# Gateway.net
KiCad netlist of a schematic drawn in Altium Designer
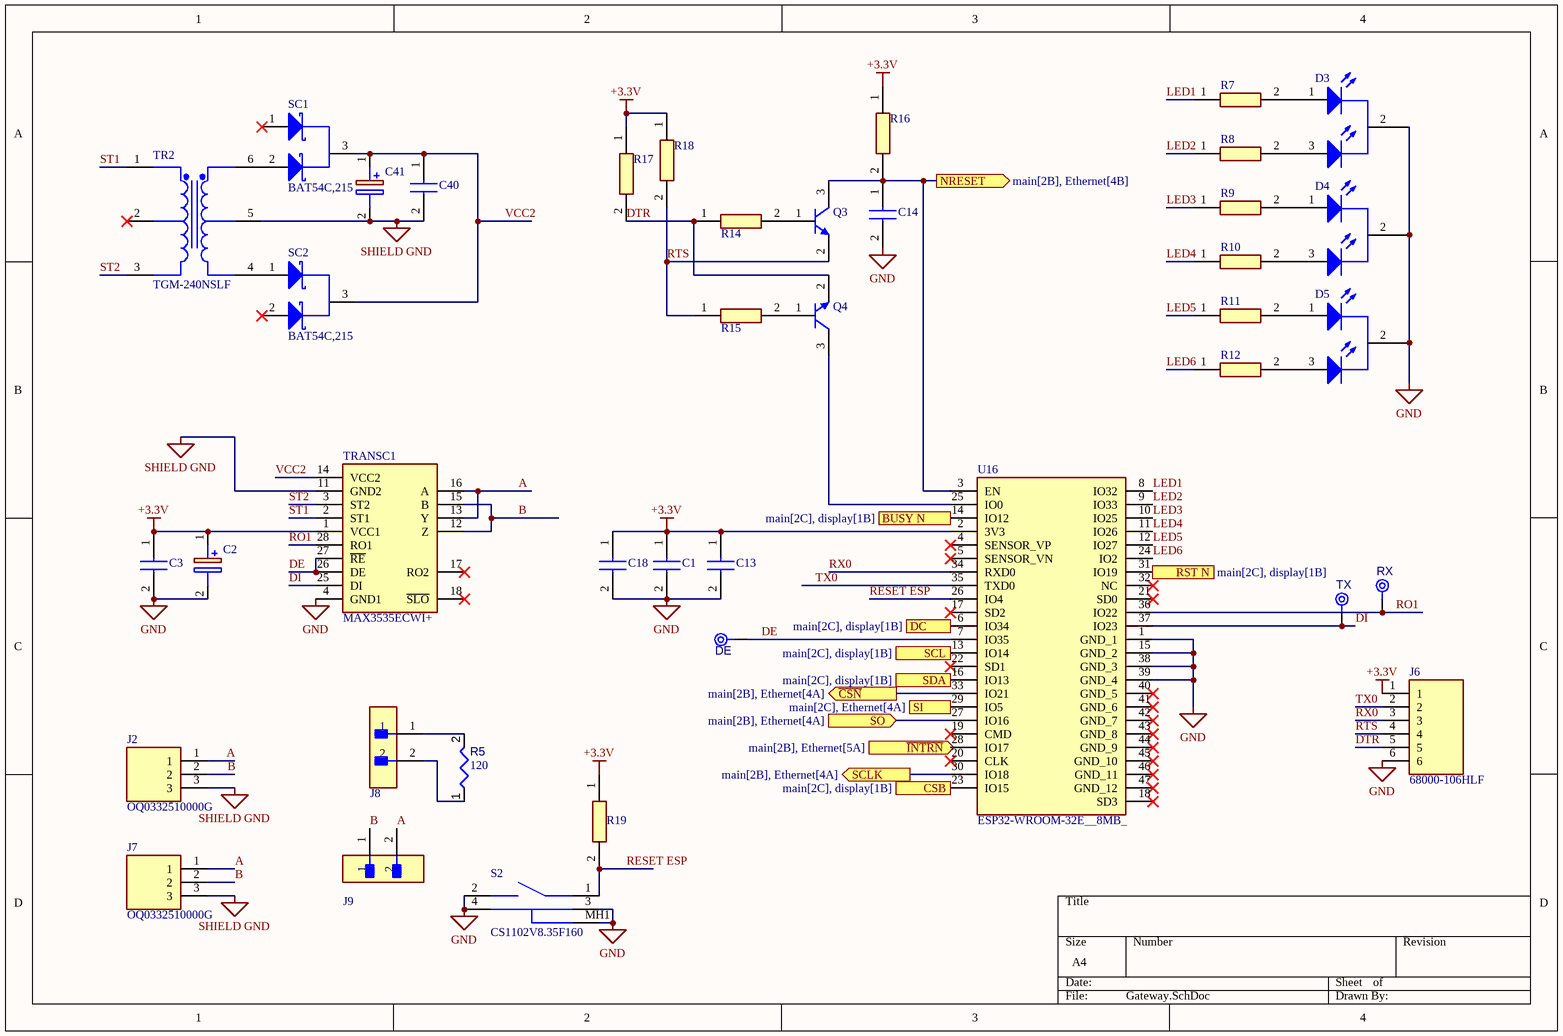
[diagram p0: Gateway.SchDoc]

(export (version "E")
  (design (tool "Eeschema 10.0.6"))
  (components
    (comp (ref "C1")
      (value "C1005X7R1C104KT")
      (footprint "SamacSys:CAPC1005X55N")
      (description "Capacitor 100n")
      (libsource (lib "*") (part "C1005X7R1C104KT"))
    )
    (comp (ref "C2")
      (value "EDH106M016A9BAA")
      (footprint "SamacSys:CAPAE430X565N")
      (description "Capacitor Polarised 10u")
      (fields (field (name "MOUSER PART NUMBER") "80-EDH106M016A9BAA"))
      (libsource (lib "*") (part "EDH106M016A9BAA"))
    )
    (comp (ref "C3")
      (value "C1005X7R1C104KT")
      (footprint "SamacSys:CAPC1005X55N")
      (description "Capacitor 100n")
      (libsource (lib "*") (part "C1005X7R1C104KT"))
    )
    (comp (ref "C13")
      (value "CL05A106MP8NUB8")
      (footprint "SamacSys:CAPC1005X90N")
      (description "Capacitor 10u")
      (fields (field (name "MOUSER PART NUMBER") "187-CL05A106MP8NUB8"))
      (libsource (lib "*") (part "CL05A106MP8NUB8"))
    )
    (comp (ref "C14")
      (value "CL05A106MP8NUB8")
      (footprint "SamacSys:CAPC1005X90N")
      (description "Capacitor 10u")
      (fields (field (name "MOUSER PART NUMBER") "187-CL05A106MP8NUB8"))
      (libsource (lib "*") (part "CL05A106MP8NUB8"))
    )
    (comp (ref "C18")
      (value "CL05B103KO5NNNC")
      (footprint "SamacSys:CAPC1005X55N")
      (description "Capacitor 10n")
      (libsource (lib "*") (part "CL05B103KO5NNNC"))
    )
    (comp (ref "C40")
      (value "C1005X7R1C104KT")
      (footprint "SamacSys:CAPC1005X55N")
      (description "Capacitor 100n")
      (libsource (lib "*") (part "C1005X7R1C104KT"))
    )
    (comp (ref "C41")
      (value "EDH106M016A9BAA")
      (footprint "SamacSys:CAPAE430X565N")
      (description "Capacitor Polarised 10u")
      (fields (field (name "MOUSER PART NUMBER") "80-EDH106M016A9BAA"))
      (libsource (lib "*") (part "EDH106M016A9BAA"))
    )
    (comp (ref "D3")
      (value "LTL1BEKVJNN")
      (footprint "Lite-On_Inc._LTL1BEKVJNN_0")
      (description "No Description Available")
      (libsource (lib "LTL1BEKVJNN") (part "LTL1BEKVJNN"))
    )
    (comp (ref "D4")
      (value "LTL1BEKVJNN")
      (footprint "Lite-On_Inc._LTL1BEKVJNN_0")
      (description "No Description Available")
      (libsource (lib "LTL1BEKVJNN") (part "LTL1BEKVJNN"))
    )
    (comp (ref "D5")
      (value "LTL1BEKVJNN")
      (footprint "Lite-On_Inc._LTL1BEKVJNN_0")
      (description "No Description Available")
      (libsource (lib "LTL1BEKVJNN") (part "LTL1BEKVJNN"))
    )
    (comp (ref "DE")
      (value "TPAD6R")
      (footprint "TP06R")
      (description "0.6mm round")
      (libsource (lib "marina santos") (part "CMP-001-0001-4"))
    )
    (comp (ref "J2")
      (value "OQ0332510000G")
      (footprint "SamacSys:SHDRRA3W80P0X381_1X3_1262X920X720P")
      (description "Connector")
      (fields (field (name "MOUSER PART NUMBER") "649-220110-D031A01LF"))
      (libsource (lib "*") (part "OQ0332510000G"))
    )
    (comp (ref "J6")
      (value "68000-106HLF")
      (footprint "HDRV6W50P0X200_1X6_1200X200X530P")
      (description "Connector")
      (fields
        (field (name "MANUFACTURER_PART_NUMBER") "M22-2010605")
        (field (name "MOUSER PART NUMBER") "855-M22-2010605")
      )
      (libsource (lib "*") (part "M22-2010605"))
    )
    (comp (ref "J7")
      (value "OQ0332510000G")
      (footprint "SamacSys:SHDRRA3W80P0X381_1X3_1262X920X720P")
      (description "Connector")
      (fields (field (name "MOUSER PART NUMBER") "649-220110-D031A01LF"))
      (libsource (lib "*") (part "OQ0332510000G"))
    )
    (comp (ref "J8")
      (value "68000-102HLF")
      (footprint "Amphenol_ICC_-_FCI_0_MFG")
      (libsource (lib "") (part "68000-102HLF_1"))
    )
    (comp (ref "J9")
      (value "68000-102HLF")
      (footprint "Amphenol_ICC_-_FCI_0_MFG")
      (libsource (lib "Conn_Amphenol_ICC_-_FCI_68000-102HLF_eec") (part "68000-102HLF"))
    )
    (comp (ref "Q3")
      (value "MMBT2222ALT1G")
      (footprint "SamacSys:SOT96P237X111-3N")
      (description "Integrated Circuit")
      (fields (field (name "MOUSER PART NUMBER") "863-MMBT2222ALT1G"))
      (libsource (lib "SamacSys") (part "MMBT2222ALT1G"))
    )
    (comp (ref "Q4")
      (value "MMBT2222ALT1G")
      (footprint "SamacSys:SOT96P237X111-3N")
      (description "Integrated Circuit")
      (fields (field (name "MOUSER PART NUMBER") "863-MMBT2222ALT1G"))
      (libsource (lib "SamacSys") (part "MMBT2222ALT1G"))
    )
    (comp (ref "R5")
      (value "120")
      (footprint "RESC0805(2012)_L")
      (description "Chip Resistor 120 ohms +1%")
      (fields (field (name "TOLERANCE") "5%") (field (name "POWER") "125mW"))
      (libsource (lib "marina santos") (part "RES-2"))
    )
    (comp (ref "R7")
      (value "RC0402FR-071KL")
      (footprint "SamacSys:RESC1005X40N")
      (description "Resistor")
      (fields (field (name "MOUSER PART NUMBER") "603-RC0402FR-071KL"))
      (libsource (lib "*") (part "RC0402FR-071KL"))
    )
    (comp (ref "R8")
      (value "RC0402FR-071KL")
      (footprint "SamacSys:RESC1005X40N")
      (description "Resistor")
      (fields (field (name "MOUSER PART NUMBER") "603-RC0402FR-071KL"))
      (libsource (lib "*") (part "RC0402FR-071KL"))
    )
    (comp (ref "R9")
      (value "RC0402FR-071KL")
      (footprint "SamacSys:RESC1005X40N")
      (description "Resistor")
      (fields (field (name "MOUSER PART NUMBER") "603-RC0402FR-071KL"))
      (libsource (lib "*") (part "RC0402FR-071KL"))
    )
    (comp (ref "R10")
      (value "RC0402FR-071KL")
      (footprint "SamacSys:RESC1005X40N")
      (description "Resistor")
      (fields (field (name "MOUSER PART NUMBER") "603-RC0402FR-071KL"))
      (libsource (lib "*") (part "RC0402FR-071KL"))
    )
    (comp (ref "R11")
      (value "RC0402FR-071KL")
      (footprint "SamacSys:RESC1005X40N")
      (description "Resistor")
      (fields (field (name "MOUSER PART NUMBER") "603-RC0402FR-071KL"))
      (libsource (lib "*") (part "RC0402FR-071KL"))
    )
    (comp (ref "R12")
      (value "RC0402FR-071KL")
      (footprint "SamacSys:RESC1005X40N")
      (description "Resistor")
      (fields (field (name "MOUSER PART NUMBER") "603-RC0402FR-071KL"))
      (libsource (lib "*") (part "RC0402FR-071KL"))
    )
    (comp (ref "R14")
      (value "RC0402FR-0710KL")
      (footprint "SamacSys:RESC1005X40N")
      (description "Resistor 10K")
      (fields (field (name "MOUSER PART NUMBER") "603-RC0402FR-0710KL"))
      (libsource (lib "") (part "RC0402FR-0710KL_1"))
    )
    (comp (ref "R15")
      (value "RC0402FR-0710KL")
      (footprint "SamacSys:RESC1005X40N")
      (description "Resistor 10K")
      (fields (field (name "MOUSER PART NUMBER") "603-RC0402FR-0710KL"))
      (libsource (lib "") (part "RC0402FR-0710KL_1"))
    )
    (comp (ref "R16")
      (value "RC0402FR-0710KL")
      (footprint "SamacSys:RESC1005X40N")
      (description "Resistor 10K")
      (fields (field (name "MOUSER PART NUMBER") "603-RC0402FR-0710KL"))
      (libsource (lib "*") (part "RC0402FR-0710KL"))
    )
    (comp (ref "R17")
      (value "RC0402FR-0710KL")
      (footprint "SamacSys:RESC1005X40N")
      (description "Resistor 10K")
      (fields (field (name "MOUSER PART NUMBER") "603-RC0402FR-0710KL"))
      (libsource (lib "*") (part "RC0402FR-0710KL"))
    )
    (comp (ref "R18")
      (value "RC0402FR-0710KL")
      (footprint "SamacSys:RESC1005X40N")
      (description "Resistor 10K")
      (fields (field (name "MOUSER PART NUMBER") "603-RC0402FR-0710KL"))
      (libsource (lib "*") (part "RC0402FR-0710KL"))
    )
    (comp (ref "R19")
      (value "RC0402FR-0710KL")
      (footprint "SamacSys:RESC1005X40N")
      (description "Resistor 10K")
      (fields (field (name "MOUSER PART NUMBER") "603-RC0402FR-0710KL"))
      (libsource (lib "*") (part "RC0402FR-0710KL"))
    )
    (comp (ref "RX")
      (value "TPAD6R")
      (footprint "TP06R")
      (description "0.6mm round")
      (libsource (lib "marina santos") (part "CMP-001-0001-4"))
    )
    (comp (ref "S2")
      (value "CS1102V8.35F160")
      (footprint "SamacSys:CS1102V385F260")
      (description "Switch")
      (fields (field (name "MANUFACTURER_PART_NUMBER") "CS1102V3.85F260"))
      (libsource (lib "SamacSys") (part "CS1102V3.85F260"))
    )
    (comp (ref "SC1")
      (value "BAT54C,215")
      (footprint "SamacSys:BAT54C215")
      (description "Schottky Diode")
      (fields (field (name "MOUSER PART NUMBER") "771-BAT54C-T/R"))
      (libsource (lib "SamacSys") (part "BAT54C,215"))
    )
    (comp (ref "SC2")
      (value "BAT54C,215")
      (footprint "SamacSys:BAT54C215")
      (description "Schottky Diode")
      (fields (field (name "MOUSER PART NUMBER") "771-BAT54C-T/R"))
      (libsource (lib "SamacSys") (part "BAT54C,215"))
    )
    (comp (ref "TR2")
      (value "TGM-240NSLF")
      (footprint "SamacSys:TGM240NSLF")
      (description "Connector")
      (fields (field (name "MOUSER PART NUMBER") "493-TGM-240NSLF"))
      (libsource (lib "SamacSys") (part "TGM-240NSLF"))
    )
    (comp (ref "TRANSC1")
      (value "MAX3535ECWI+")
      (footprint "SamacSys:MAX3535ECWI")
      (description "Integrated Circuit")
      (fields (field (name "MOUSER PART NUMBER") "700-MAX3535ECWI"))
      (libsource (lib "SamacSys") (part "MAX3535ECWI+"))
    )
    (comp (ref "TX")
      (value "TPAD6R")
      (footprint "TP06R")
      (description "0.6mm round")
      (libsource (lib "marina santos") (part "CMP-001-0001-4"))
    )
    (comp (ref "U16")
      (value "ESP32-WROOM-32E__8MB_")
      (footprint "SamacSys:ESP32WROOM32E8MB")
      (description "Integrated Circuit")
      (fields
        (field (name "MANUFACTURER_PART_NUMBER") "ESP32-WROOM-32E (8MB)")
        (field (name "MOUSER PART NUMBER") "356-ESP32WRM32E164PH")
      )
      (libsource (lib "SamacSys") (part "ESP32-WROOM-32E__8MB_"))
    )
  )
  (nets
    (net (code "1") (name "+3.3V") (class "Default")
      (node (ref "C1") (pin "1") (pinfunction "1_1") (pintype "passive"))
      (node (ref "C13") (pin "1") (pinfunction "1_1") (pintype "passive"))
      (node (ref "C18") (pin "1") (pinfunction "1_1") (pintype "passive"))
      (node (ref "C2") (pin "1") (pinfunction "+_1") (pintype "passive"))
      (node (ref "C3") (pin "1") (pinfunction "1_1") (pintype "passive"))
      (node (ref "J6") (pin "1") (pinfunction "1_1") (pintype "passive"))
      (node (ref "R16") (pin "1") (pinfunction "1_1") (pintype "passive"))
      (node (ref "R17") (pin "1") (pinfunction "1_1") (pintype "passive"))
      (node (ref "R18") (pin "1") (pinfunction "1_1") (pintype "passive"))
      (node (ref "R19") (pin "1") (pinfunction "1_1") (pintype "passive"))
      (node (ref "TRANSC1") (pin "1") (pinfunction "VCC1_1") (pintype "passive"))
      (node (ref "U16") (pin "2") (pinfunction "3V3_2") (pintype "passive"))
    )
    (net (code "2") (name "/A") (class "Default")
      (node (ref "J2") (pin "1") (pinfunction "1_1") (pintype "passive"))
      (node (ref "J7") (pin "1") (pinfunction "1_1") (pintype "passive"))
      (node (ref "J9") (pin "2") (pinfunction "2_2") (pintype "passive"))
      (node (ref "TRANSC1") (pin "13") (pinfunction "Y_13") (pintype "passive"))
      (node (ref "TRANSC1") (pin "16") (pinfunction "A_16") (pintype "passive"))
    )
    (net (code "3") (name "/B") (class "Default")
      (node (ref "J2") (pin "2") (pinfunction "2_2") (pintype "passive"))
      (node (ref "J7") (pin "2") (pinfunction "2_2") (pintype "passive"))
      (node (ref "J9") (pin "1") (pinfunction "1_1") (pintype "passive"))
      (node (ref "TRANSC1") (pin "12") (pinfunction "Z_12") (pintype "passive"))
      (node (ref "TRANSC1") (pin "15") (pinfunction "B_15") (pintype "passive"))
    )
    (net (code "4") (name "/BUSY N") (class "Default")
      (node (ref "U16") (pin "14") (pinfunction "IO12_14") (pintype "passive"))
    )
    (net (code "5") (name "/CSB") (class "Default")
      (node (ref "U16") (pin "23") (pinfunction "IO15_23") (pintype "passive"))
    )
    (net (code "6") (name "/DC") (class "Default")
      (node (ref "U16") (pin "6") (pinfunction "IO34_6") (pintype "passive"))
    )
    (net (code "7") (name "/DE") (class "Default")
      (node (ref "DE") (pin "1") (pinfunction "TP_1") (pintype "passive"))
      (node (ref "TRANSC1") (pin "26") (pinfunction "DE_26") (pintype "passive"))
      (node (ref "TRANSC1") (pin "27") (pinfunction "~{RE}_27") (pintype "passive"))
      (node (ref "U16") (pin "7") (pinfunction "IO35_7") (pintype "passive"))
    )
    (net (code "8") (name "/DI") (class "Default")
      (node (ref "TRANSC1") (pin "25") (pinfunction "DI_25") (pintype "passive"))
      (node (ref "TX") (pin "1") (pinfunction "TP_1") (pintype "passive"))
      (node (ref "U16") (pin "37") (pinfunction "IO23_37") (pintype "passive"))
    )
    (net (code "9") (name "/DTR") (class "Default")
      (node (ref "J6") (pin "5") (pinfunction "5_5") (pintype "passive"))
      (node (ref "Q4") (pin "2") (pinfunction "E_2") (pintype "passive"))
      (node (ref "R14") (pin "1") (pinfunction "1_1") (pintype "passive"))
      (node (ref "R17") (pin "2") (pinfunction "2_2") (pintype "passive"))
    )
    (net (code "10") (name "/LED1") (class "Default")
      (node (ref "R7") (pin "1") (pinfunction "1_1") (pintype "passive"))
      (node (ref "U16") (pin "8") (pinfunction "IO32_8") (pintype "passive"))
    )
    (net (code "11") (name "/LED2") (class "Default")
      (node (ref "R8") (pin "1") (pinfunction "1_1") (pintype "passive"))
      (node (ref "U16") (pin "9") (pinfunction "IO33_9") (pintype "passive"))
    )
    (net (code "12") (name "/LED3") (class "Default")
      (node (ref "R9") (pin "1") (pinfunction "1_1") (pintype "passive"))
      (node (ref "U16") (pin "10") (pinfunction "IO25_10") (pintype "passive"))
    )
    (net (code "13") (name "/LED4") (class "Default")
      (node (ref "R10") (pin "1") (pinfunction "1_1") (pintype "passive"))
      (node (ref "U16") (pin "11") (pinfunction "IO26_11") (pintype "passive"))
    )
    (net (code "14") (name "/LED5") (class "Default")
      (node (ref "R11") (pin "1") (pinfunction "1_1") (pintype "passive"))
      (node (ref "U16") (pin "12") (pinfunction "IO27_12") (pintype "passive"))
    )
    (net (code "15") (name "/LED6") (class "Default")
      (node (ref "R12") (pin "1") (pinfunction "1_1") (pintype "passive"))
      (node (ref "U16") (pin "24") (pinfunction "IO2_24") (pintype "passive"))
    )
    (net (code "16") (name "/NRESET") (class "Default")
      (node (ref "C14") (pin "1") (pinfunction "1_1") (pintype "passive"))
      (node (ref "Q3") (pin "3") (pinfunction "C_3") (pintype "passive"))
      (node (ref "R16") (pin "2") (pinfunction "2_2") (pintype "passive"))
      (node (ref "U16") (pin "3") (pinfunction "EN_3") (pintype "passive"))
    )
    (net (code "17") (name "/RESET ESP") (class "Default")
      (node (ref "R19") (pin "2") (pinfunction "2_2") (pintype "passive"))
      (node (ref "S2") (pin "1") (pinfunction "NO_1") (pintype "passive"))
      (node (ref "U16") (pin "26") (pinfunction "IO4_26") (pintype "passive"))
    )
    (net (code "18") (name "/RO1") (class "Default")
      (node (ref "RX") (pin "1") (pinfunction "TP_1") (pintype "passive"))
      (node (ref "TRANSC1") (pin "28") (pinfunction "RO1_28") (pintype "passive"))
      (node (ref "U16") (pin "36") (pinfunction "IO22_36") (pintype "passive"))
    )
    (net (code "19") (name "/RST N") (class "Default")
      (node (ref "U16") (pin "31") (pinfunction "IO19_31") (pintype "passive"))
    )
    (net (code "20") (name "/RTS") (class "Default")
      (node (ref "J6") (pin "4") (pinfunction "4_4") (pintype "passive"))
      (node (ref "Q3") (pin "2") (pinfunction "E_2") (pintype "passive"))
      (node (ref "R15") (pin "1") (pinfunction "1_1") (pintype "passive"))
      (node (ref "R18") (pin "2") (pinfunction "2_2") (pintype "passive"))
    )
    (net (code "21") (name "/RX0") (class "Default")
      (node (ref "J6") (pin "3") (pinfunction "3_3") (pintype "passive"))
      (node (ref "U16") (pin "34") (pinfunction "RXD0_34") (pintype "passive"))
    )
    (net (code "22") (name "/SCL") (class "Default")
      (node (ref "U16") (pin "13") (pinfunction "IO14_13") (pintype "passive"))
    )
    (net (code "23") (name "/SCLK") (class "Default")
      (node (ref "U16") (pin "30") (pinfunction "IO18_30") (pintype "passive"))
    )
    (net (code "24") (name "/SDA") (class "Default")
      (node (ref "U16") (pin "16") (pinfunction "IO13_16") (pintype "passive"))
    )
    (net (code "25") (name "/SI") (class "Default")
      (node (ref "U16") (pin "29") (pinfunction "IO5_29") (pintype "passive"))
    )
    (net (code "26") (name "/SO") (class "Default")
      (node (ref "U16") (pin "27") (pinfunction "IO16_27") (pintype "passive"))
    )
    (net (code "27") (name "/ST1") (class "Default")
      (node (ref "TR2") (pin "1") (pinfunction "PRI_1_1") (pintype "passive"))
      (node (ref "TRANSC1") (pin "2") (pinfunction "ST1_2") (pintype "passive"))
    )
    (net (code "28") (name "/ST2") (class "Default")
      (node (ref "TR2") (pin "3") (pinfunction "PRI_3_3") (pintype "passive"))
      (node (ref "TRANSC1") (pin "3") (pinfunction "ST2_3") (pintype "passive"))
    )
    (net (code "29") (name "/TX0") (class "Default")
      (node (ref "J6") (pin "2") (pinfunction "2_2") (pintype "passive"))
      (node (ref "U16") (pin "35") (pinfunction "TXD0_35") (pintype "passive"))
    )
    (net (code "30") (name "/VCC2") (class "Default")
      (node (ref "C40") (pin "1") (pinfunction "1_1") (pintype "passive"))
      (node (ref "C41") (pin "1") (pinfunction "+_1") (pintype "passive"))
      (node (ref "SC1") (pin "3") (pinfunction "COMMON_CATHODE_3") (pintype "passive"))
      (node (ref "SC2") (pin "3") (pinfunction "COMMON_CATHODE_3") (pintype "passive"))
      (node (ref "TRANSC1") (pin "14") (pinfunction "VCC2_14") (pintype "passive"))
    )
    (net (code "31") (name "/~{CSN}") (class "Default")
      (node (ref "U16") (pin "33") (pinfunction "IO21_33") (pintype "passive"))
    )
    (net (code "32") (name "/~{INTRN}") (class "Default")
      (node (ref "U16") (pin "28") (pinfunction "IO17_28") (pintype "passive"))
    )
    (net (code "33") (name "GND") (class "Default")
      (node (ref "C1") (pin "2") (pinfunction "2_2") (pintype "passive"))
      (node (ref "C13") (pin "2") (pinfunction "2_2") (pintype "passive"))
      (node (ref "C14") (pin "2") (pinfunction "2_2") (pintype "passive"))
      (node (ref "C18") (pin "2") (pinfunction "2_2") (pintype "passive"))
      (node (ref "C2") (pin "2") (pinfunction "-_2") (pintype "passive"))
      (node (ref "C3") (pin "2") (pinfunction "2_2") (pintype "passive"))
      (node (ref "D3") (pin "2") (pinfunction "COMMONCATHODE_2") (pintype "passive"))
      (node (ref "D4") (pin "2") (pinfunction "COMMONCATHODE_2") (pintype "passive"))
      (node (ref "D5") (pin "2") (pinfunction "COMMONCATHODE_2") (pintype "passive"))
      (node (ref "J6") (pin "6") (pinfunction "6_6") (pintype "passive"))
      (node (ref "S2") (pin "2") (pinfunction "COM_2") (pintype "passive"))
      (node (ref "S2") (pin "3") (pinfunction "GND_1_3") (pintype "passive"))
      (node (ref "S2") (pin "4") (pinfunction "GND_2_4") (pintype "passive"))
      (node (ref "S2") (pin "MH1") (pinfunction "MH1_MH1") (pintype "passive"))
      (node (ref "TRANSC1") (pin "4") (pinfunction "GND1_4") (pintype "passive"))
      (node (ref "U16") (pin "1") (pinfunction "GND_1_1") (pintype "passive"))
      (node (ref "U16") (pin "15") (pinfunction "GND_2_15") (pintype "passive"))
      (node (ref "U16") (pin "38") (pinfunction "GND_3_38") (pintype "passive"))
      (node (ref "U16") (pin "39") (pinfunction "GND_4_39") (pintype "passive"))
    )
    (net (code "34") (name "Net-(D3-GREENANODE)") (class "Default")
      (node (ref "D3") (pin "3") (pinfunction "GREENANODE_3") (pintype "passive"))
      (node (ref "R8") (pin "2") (pinfunction "2_2") (pintype "passive"))
    )
    (net (code "35") (name "Net-(D3-REDANODE)") (class "Default")
      (node (ref "D3") (pin "1") (pinfunction "REDANODE_1") (pintype "passive"))
      (node (ref "R7") (pin "2") (pinfunction "2_2") (pintype "passive"))
    )
    (net (code "36") (name "Net-(D4-GREENANODE)") (class "Default")
      (node (ref "D4") (pin "3") (pinfunction "GREENANODE_3") (pintype "passive"))
      (node (ref "R10") (pin "2") (pinfunction "2_2") (pintype "passive"))
    )
    (net (code "37") (name "Net-(D4-REDANODE)") (class "Default")
      (node (ref "D4") (pin "1") (pinfunction "REDANODE_1") (pintype "passive"))
      (node (ref "R9") (pin "2") (pinfunction "2_2") (pintype "passive"))
    )
    (net (code "38") (name "Net-(D5-GREENANODE)") (class "Default")
      (node (ref "D5") (pin "3") (pinfunction "GREENANODE_3") (pintype "passive"))
      (node (ref "R12") (pin "2") (pinfunction "2_2") (pintype "passive"))
    )
    (net (code "39") (name "Net-(D5-REDANODE)") (class "Default")
      (node (ref "D5") (pin "1") (pinfunction "REDANODE_1") (pintype "passive"))
      (node (ref "R11") (pin "2") (pinfunction "2_2") (pintype "passive"))
    )
    (net (code "40") (name "Net-(J8-Pad1)") (class "Default")
      (node (ref "J8") (pin "1") (pinfunction "1_1") (pintype "passive"))
      (node (ref "R5") (pin "2") (pinfunction "2_2") (pintype "passive"))
    )
    (net (code "41") (name "Net-(J8-Pad2)") (class "Default")
      (node (ref "J8") (pin "2") (pinfunction "2_2") (pintype "passive"))
      (node (ref "R5") (pin "1") (pinfunction "1_1") (pintype "passive"))
    )
    (net (code "42") (name "Net-(Q3-B)") (class "Default")
      (node (ref "Q3") (pin "1") (pinfunction "B_1") (pintype "passive"))
      (node (ref "R14") (pin "2") (pinfunction "2_2") (pintype "passive"))
    )
    (net (code "43") (name "Net-(Q4-B)") (class "Default")
      (node (ref "Q4") (pin "1") (pinfunction "B_1") (pintype "passive"))
      (node (ref "R15") (pin "2") (pinfunction "2_2") (pintype "passive"))
    )
    (net (code "44") (name "Net-(Q4-C)") (class "Default")
      (node (ref "Q4") (pin "3") (pinfunction "C_3") (pintype "passive"))
      (node (ref "U16") (pin "25") (pinfunction "IO0_25") (pintype "passive"))
    )
    (net (code "45") (name "Net-(SC1-ANODE_2)") (class "Default")
      (node (ref "SC1") (pin "2") (pinfunction "ANODE_2_2") (pintype "passive"))
      (node (ref "TR2") (pin "6") (pinfunction "SEC_3_6") (pintype "passive"))
    )
    (net (code "46") (name "Net-(SC2-ANODE_1)") (class "Default")
      (node (ref "SC2") (pin "1") (pinfunction "ANODE_1_1") (pintype "passive"))
      (node (ref "TR2") (pin "4") (pinfunction "SEC_1_4") (pintype "passive"))
    )
    (net (code "47") (name "SHIELD GND") (class "Default")
      (node (ref "C40") (pin "2") (pinfunction "2_2") (pintype "passive"))
      (node (ref "C41") (pin "2") (pinfunction "-_2") (pintype "passive"))
      (node (ref "J2") (pin "3") (pinfunction "3_3") (pintype "passive"))
      (node (ref "J7") (pin "3") (pinfunction "3_3") (pintype "passive"))
      (node (ref "TR2") (pin "5") (pinfunction "SEC_2_5") (pintype "passive"))
      (node (ref "TRANSC1") (pin "11") (pinfunction "GND2_11") (pintype "passive"))
    )
    (net (code "48") (name "unconnected-(SC1-ANODE_1-Pad1)") (class "Default")
      (node (ref "SC1") (pin "1") (pinfunction "ANODE_1_1") (pintype "passive+no_connect"))
    )
    (net (code "49") (name "unconnected-(SC2-ANODE_2-Pad2)") (class "Default")
      (node (ref "SC2") (pin "2") (pinfunction "ANODE_2_2") (pintype "passive+no_connect"))
    )
    (net (code "50") (name "unconnected-(TR2-PRI_2-Pad2)") (class "Default")
      (node (ref "TR2") (pin "2") (pinfunction "PRI_2_2") (pintype "passive+no_connect"))
    )
    (net (code "51") (name "unconnected-(TRANSC1-RO2-Pad17)") (class "Default")
      (node (ref "TRANSC1") (pin "17") (pinfunction "RO2_17") (pintype "passive+no_connect"))
    )
    (net (code "52") (name "unconnected-(TRANSC1-~{SLO}-Pad18)") (class "Default")
      (node (ref "TRANSC1") (pin "18") (pinfunction "~{SLO}_18") (pintype "passive+no_connect"))
    )
    (net (code "53") (name "unconnected-(U16-CLK-Pad20)") (class "Default")
      (node (ref "U16") (pin "20") (pinfunction "CLK_20") (pintype "passive+no_connect"))
    )
    (net (code "54") (name "unconnected-(U16-CMD-Pad19)") (class "Default")
      (node (ref "U16") (pin "19") (pinfunction "CMD_19") (pintype "passive+no_connect"))
    )
    (net (code "55") (name "unconnected-(U16-GND_5-Pad40)") (class "Default")
      (node (ref "U16") (pin "40") (pinfunction "GND_5_40") (pintype "passive+no_connect"))
    )
    (net (code "56") (name "unconnected-(U16-GND_6-Pad41)") (class "Default")
      (node (ref "U16") (pin "41") (pinfunction "GND_6_41") (pintype "passive+no_connect"))
    )
    (net (code "57") (name "unconnected-(U16-GND_7-Pad42)") (class "Default")
      (node (ref "U16") (pin "42") (pinfunction "GND_7_42") (pintype "passive+no_connect"))
    )
    (net (code "58") (name "unconnected-(U16-GND_8-Pad43)") (class "Default")
      (node (ref "U16") (pin "43") (pinfunction "GND_8_43") (pintype "passive+no_connect"))
    )
    (net (code "59") (name "unconnected-(U16-GND_9-Pad44)") (class "Default")
      (node (ref "U16") (pin "44") (pinfunction "GND_9_44") (pintype "passive+no_connect"))
    )
    (net (code "60") (name "unconnected-(U16-GND_10-Pad45)") (class "Default")
      (node (ref "U16") (pin "45") (pinfunction "GND_10_45") (pintype "passive+no_connect"))
    )
    (net (code "61") (name "unconnected-(U16-GND_11-Pad46)") (class "Default")
      (node (ref "U16") (pin "46") (pinfunction "GND_11_46") (pintype "passive+no_connect"))
    )
    (net (code "62") (name "unconnected-(U16-GND_12-Pad47)") (class "Default")
      (node (ref "U16") (pin "47") (pinfunction "GND_12_47") (pintype "passive+no_connect"))
    )
    (net (code "63") (name "unconnected-(U16-NC-Pad32)") (class "Default")
      (node (ref "U16") (pin "32") (pinfunction "NC_32") (pintype "passive+no_connect"))
    )
    (net (code "64") (name "unconnected-(U16-SD0-Pad21)") (class "Default")
      (node (ref "U16") (pin "21") (pinfunction "SD0_21") (pintype "passive+no_connect"))
    )
    (net (code "65") (name "unconnected-(U16-SD1-Pad22)") (class "Default")
      (node (ref "U16") (pin "22") (pinfunction "SD1_22") (pintype "passive+no_connect"))
    )
    (net (code "66") (name "unconnected-(U16-SD2-Pad17)") (class "Default")
      (node (ref "U16") (pin "17") (pinfunction "SD2_17") (pintype "passive+no_connect"))
    )
    (net (code "67") (name "unconnected-(U16-SD3-Pad18)") (class "Default")
      (node (ref "U16") (pin "18") (pinfunction "SD3_18") (pintype "passive+no_connect"))
    )
    (net (code "68") (name "unconnected-(U16-SENSOR_VN-Pad5)") (class "Default")
      (node (ref "U16") (pin "5") (pinfunction "SENSOR_VN_5") (pintype "passive+no_connect"))
    )
    (net (code "69") (name "unconnected-(U16-SENSOR_VP-Pad4)") (class "Default")
      (node (ref "U16") (pin "4") (pinfunction "SENSOR_VP_4") (pintype "passive+no_connect"))
    )
  )
)
